# uc_relay.net
KiCad netlist of a schematic drawn in EAGLE
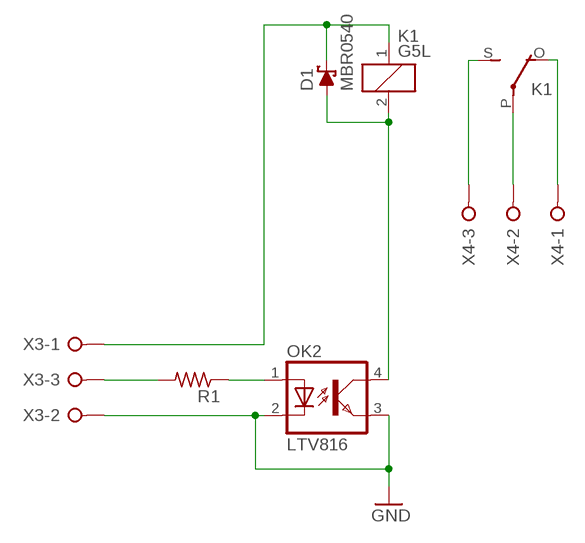
[diagram p0: schematic, sheet 1]

(export (version "E")
  (design (tool "Eeschema 10.0.6"))
  (components
    (comp (ref "D1")
      (value "MBR0540")
      (footprint "eagle-import:SOD123")
      (libsource (lib "eagle-import") (part "MBR0540"))
    )
    (comp (ref "K1")
      (value "G5L")
      (footprint "eagle-import:G5LE")
      (libsource (lib "eagle-import") (part "G5L"))
    )
    (comp (ref "OK2")
      (value "LTV816")
      (footprint "eagle-import:DIL04")
      (libsource (lib "eagle-import") (part "LTV816"))
    )
    (comp (ref "R1")
      (value "R-US_R0805")
      (footprint "eagle-import:R0805")
      (libsource (lib "eagle-import") (part "R-US_R0805"))
    )
    (comp (ref "X3")
      (value "W237-3E")
      (footprint "eagle-import:W237-3E")
      (libsource (lib "eagle-import") (part "W237-3E"))
    )
    (comp (ref "X4")
      (value "W237-3E")
      (footprint "eagle-import:W237-3E")
      (libsource (lib "eagle-import") (part "W237-3E"))
    )
  )
  (nets
    (net (code "1") (name "GND") (class "Default")
      (node (ref "OK2") (pin "2") (pinfunction "C_2") (pintype "passive"))
      (node (ref "OK2") (pin "3") (pinfunction "EMIT_3") (pintype "passive"))
      (node (ref "X3") (pin "2") (pinfunction "KL_2") (pintype "passive"))
    )
    (net (code "2") (name "Net-(OK2-A)") (class "Default")
      (node (ref "OK2") (pin "1") (pinfunction "A_1") (pintype "passive"))
      (node (ref "R1") (pin "1") (pinfunction "1_1") (pintype "passive"))
    )
    (net (code "3") (name "Net-(OK2-COL)") (class "Default")
      (node (ref "D1") (pin "A") (pinfunction "A_A") (pintype "passive"))
      (node (ref "K1") (pin "2") (pinfunction "2_2") (pintype "passive"))
      (node (ref "OK2") (pin "4") (pinfunction "COL_4") (pintype "passive"))
    )
    (net (code "4") (name "Net-(X3A-KL)") (class "Default")
      (node (ref "D1") (pin "C") (pinfunction "C_C") (pintype "passive"))
      (node (ref "K1") (pin "1") (pinfunction "1_1") (pintype "passive"))
      (node (ref "X3") (pin "1") (pinfunction "KL_1") (pintype "passive"))
    )
    (net (code "5") (name "Net-(X3C-KL)") (class "Default")
      (node (ref "R1") (pin "2") (pinfunction "2_2") (pintype "passive"))
      (node (ref "X3") (pin "3") (pinfunction "KL_3") (pintype "passive"))
    )
    (net (code "6") (name "Net-(X4A-KL)") (class "Default")
      (node (ref "K1") (pin "O") (pinfunction "O_O") (pintype "passive"))
      (node (ref "X4") (pin "1") (pinfunction "KL_1") (pintype "passive"))
    )
    (net (code "7") (name "Net-(X4B-KL)") (class "Default")
      (node (ref "K1") (pin "P") (pinfunction "P_P") (pintype "passive"))
      (node (ref "X4") (pin "2") (pinfunction "KL_2") (pintype "passive"))
    )
    (net (code "8") (name "Net-(X4C-KL)") (class "Default")
      (node (ref "K1") (pin "S") (pinfunction "S_S") (pintype "passive"))
      (node (ref "X4") (pin "3") (pinfunction "KL_3") (pintype "passive"))
    )
  )
)
